# Single_Item_Sensor.net
KiCad netlist of a schematic drawn in EAGLE
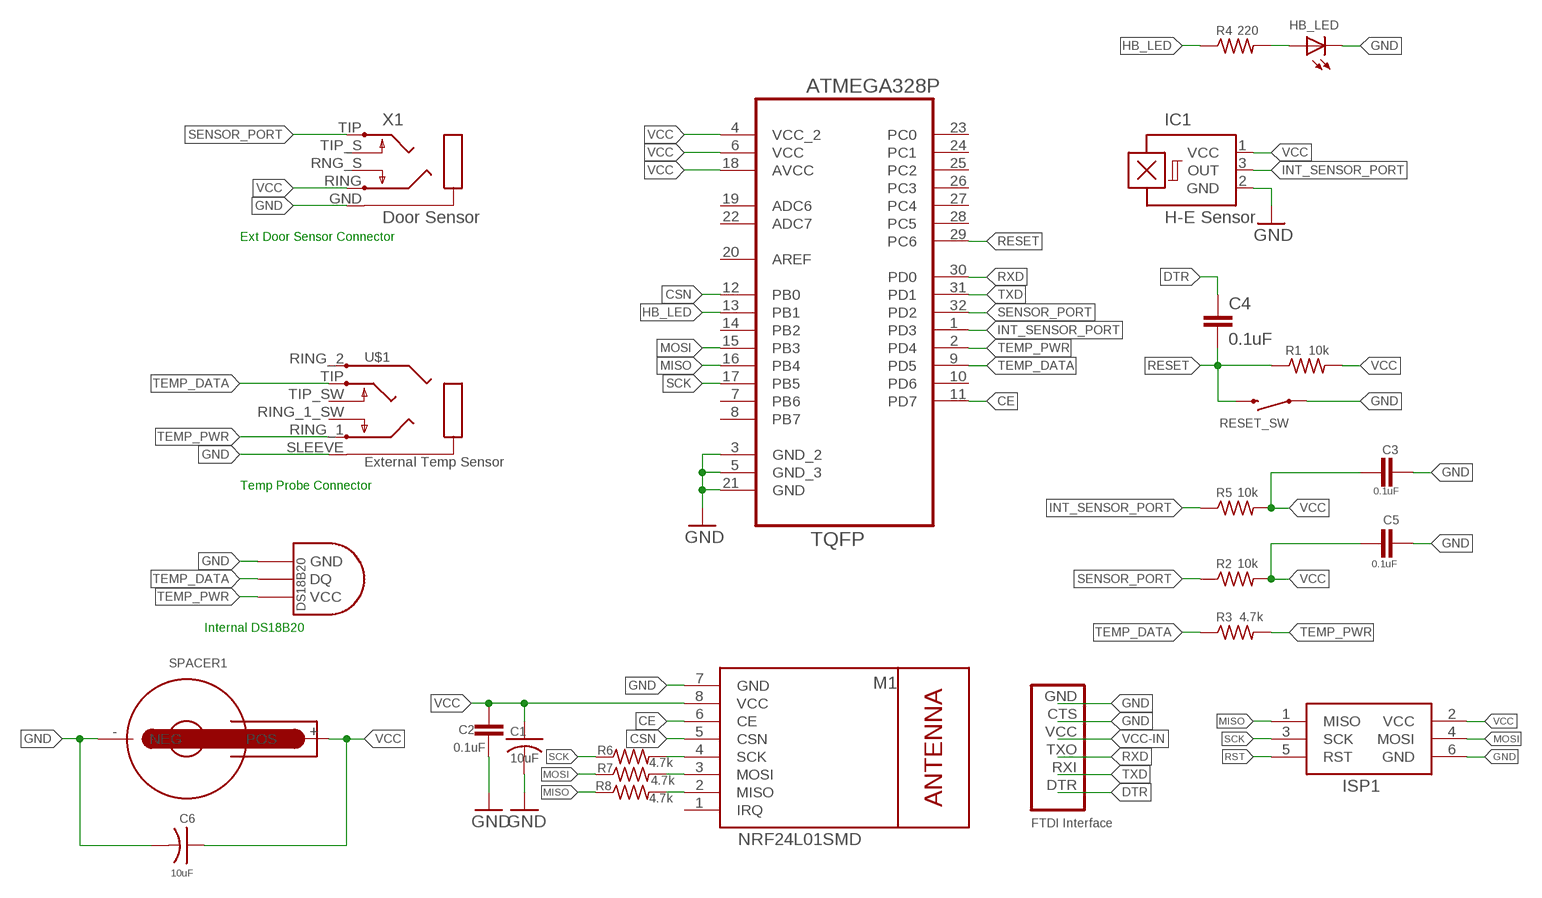
[diagram p0: schematic, sheet 1]

(export (version "E")
  (design (tool "Eeschema 10.0.6"))
  (components
    (comp (ref "C1")
      (value "10uF")
      (footprint "eagle-import:C1206")
      (libsource (lib "eagle-import") (part "C-USC1206"))
    )
    (comp (ref "C2")
      (value "0.1uF")
      (footprint "eagle-import:0805")
      (libsource (lib "eagle-import") (part "CAP0805"))
    )
    (comp (ref "C3")
      (value "0.1uF")
      (footprint "eagle-import:0805")
      (libsource (lib "eagle-import") (part "CAP0805"))
    )
    (comp (ref "C4")
      (value "0.1uF")
      (footprint "eagle-import:0805")
      (libsource (lib "eagle-import") (part "CAP0805"))
    )
    (comp (ref "C5")
      (value "0.1uF")
      (footprint "eagle-import:0805")
      (libsource (lib "eagle-import") (part "CAP0805"))
    )
    (comp (ref "C6")
      (value "10uF")
      (footprint "eagle-import:C1206")
      (libsource (lib "eagle-import") (part "C-USC1206"))
    )
    (comp (ref "HB_LED")
      (value "LEDCHIP-LED0603")
      (footprint "eagle-import:CHIP-LED0603")
      (libsource (lib "eagle-import") (part "LEDCHIP-LED0603"))
    )
    (comp (ref "IC1")
      (value "H-E Sensor")
      (footprint "eagle-import:SIP3-UA")
      (libsource (lib "eagle-import") (part "A12?UA02"))
    )
    (comp (ref "ISP1")
      (value "AVRISP-6")
      (footprint "eagle-import:AVRISP")
      (libsource (lib "eagle-import") (part "AVRISP-6"))
    )
    (comp (ref "M1")
      (value "NRF24L01SMD")
      (footprint "eagle-import:WIRELESS-NRF24L01-SMD")
      (libsource (lib "eagle-import") (part "WIRELESS-NRF24L01SMD"))
    )
    (comp (ref "R1")
      (value "10k")
      (footprint "eagle-import:M0805")
      (libsource (lib "eagle-import") (part "R-US_M0805"))
    )
    (comp (ref "R2")
      (value "10k")
      (footprint "eagle-import:M0805")
      (libsource (lib "eagle-import") (part "R-US_M0805"))
    )
    (comp (ref "R3")
      (value "4.7k")
      (footprint "eagle-import:M0805")
      (libsource (lib "eagle-import") (part "R-US_M0805"))
    )
    (comp (ref "R4")
      (value "220")
      (footprint "eagle-import:M0805")
      (libsource (lib "eagle-import") (part "R-US_M0805"))
    )
    (comp (ref "R5")
      (value "10k")
      (footprint "eagle-import:M0805")
      (libsource (lib "eagle-import") (part "R-US_M0805"))
    )
    (comp (ref "R6")
      (value "4.7k")
      (footprint "eagle-import:M0805")
      (libsource (lib "eagle-import") (part "R-US_M0805"))
    )
    (comp (ref "R7")
      (value "4.7k")
      (footprint "eagle-import:M0805")
      (libsource (lib "eagle-import") (part "R-US_M0805"))
    )
    (comp (ref "R8")
      (value "4.7k")
      (footprint "eagle-import:M0805")
      (libsource (lib "eagle-import") (part "R-US_M0805"))
    )
    (comp (ref "RESET_SW")
      (value "Reset")
      (footprint "eagle-import:TACTILE-SWITCH-1101NE")
      (libsource (lib "eagle-import") (part "SWITCH-MOMENTARY-2-SMD-1101NE"))
    )
    (comp (ref "SPACER1")
      (value "WA-BCPH_SMT_79527141")
      (footprint "eagle-import:79527141")
      (libsource (lib "eagle-import") (part "WA-BCPH_SMT_79527141"))
    )
    (comp (ref "U$1")
      (value "External Temp Sensor")
      (footprint "eagle-import:PJ-242")
      (libsource (lib "eagle-import") (part "PJ-242"))
    )
    (comp (ref "U$2")
      (value "DS1820TO92")
      (footprint "eagle-import:DS1820")
      (libsource (lib "eagle-import") (part "DS1820TO92"))
    )
    (comp (ref "U$3")
      (value "FTDI Interface")
      (footprint "eagle-import:1X6-FTDI")
      (libsource (lib "eagle-import") (part "FTDI-HEADER"))
    )
    (comp (ref "U1")
      (value "ATMEGA328P-AU")
      (footprint "eagle-import:QFP80P900X900X120-32N")
      (libsource (lib "eagle-import") (part "ATMEGA328P-AU"))
    )
    (comp (ref "X1")
      (value "Door Sensor")
      (footprint "eagle-import:PG203J")
      (libsource (lib "eagle-import") (part "PG203JPJ-328"))
    )
  )
  (nets
    (net (code "1") (name "CE") (class "Default")
      (node (ref "M1") (pin "6") (pinfunction "CE_6") (pintype "bidirectional"))
      (node (ref "U1") (pin "11") (pinfunction "PD7_11") (pintype "bidirectional"))
    )
    (net (code "2") (name "CSN") (class "Default")
      (node (ref "M1") (pin "5") (pinfunction "CSN_5") (pintype "bidirectional"))
      (node (ref "U1") (pin "12") (pinfunction "PB0_12") (pintype "bidirectional"))
    )
    (net (code "3") (name "DTR") (class "Default")
      (node (ref "C4") (pin "1") (pinfunction "1_1") (pintype "passive"))
      (node (ref "U$3") (pin "DTR") (pinfunction "DTR_DTR") (pintype "passive"))
    )
    (net (code "4") (name "GND") (class "Default")
      (node (ref "C1") (pin "2") (pinfunction "2_2") (pintype "passive"))
      (node (ref "C2") (pin "2") (pinfunction "2_2") (pintype "passive"))
      (node (ref "C3") (pin "2") (pinfunction "2_2") (pintype "passive"))
      (node (ref "C5") (pin "2") (pinfunction "2_2") (pintype "passive"))
      (node (ref "C6") (pin "2") (pinfunction "2_2") (pintype "passive"))
      (node (ref "HB_LED") (pin "C") (pinfunction "C_C") (pintype "passive"))
      (node (ref "IC1") (pin "2") (pinfunction "GND_2") (pintype "power_in"))
      (node (ref "ISP1") (pin "6") (pinfunction "GND_6") (pintype "power_in"))
      (node (ref "M1") (pin "7") (pinfunction "GND_7") (pintype "power_in"))
      (node (ref "RESET_SW") (pin "P$1") (pinfunction "1_P$1") (pintype "passive"))
      (node (ref "SPACER1") (pin "-") (pinfunction "NEG_-") (pintype "bidirectional"))
      (node (ref "U$1") (pin "SLEEVE") (pinfunction "5_SLEEVE") (pintype "passive"))
      (node (ref "U$2") (pin "GND") (pinfunction "GND_GND") (pintype "power_in"))
      (node (ref "U$3") (pin "CTS") (pinfunction "CTS_CTS") (pintype "passive"))
      (node (ref "U$3") (pin "GND") (pinfunction "GND_GND") (pintype "passive"))
      (node (ref "U1") (pin "21") (pinfunction "GND_21") (pintype "passive"))
      (node (ref "U1") (pin "3") (pinfunction "GND_2_3") (pintype "passive"))
      (node (ref "U1") (pin "5") (pinfunction "GND_3_5") (pintype "passive"))
      (node (ref "X1") (pin "GND") (pinfunction "1_GND") (pintype "passive"))
    )
    (net (code "5") (name "HB_LED") (class "Default")
      (node (ref "R4") (pin "1") (pinfunction "1_1") (pintype "passive"))
      (node (ref "U1") (pin "13") (pinfunction "PB1_13") (pintype "bidirectional"))
    )
    (net (code "6") (name "INT_SENSOR_PORT") (class "Default")
      (node (ref "IC1") (pin "3") (pinfunction "OUT_3") (pintype "output"))
      (node (ref "R5") (pin "1") (pinfunction "1_1") (pintype "passive"))
      (node (ref "U1") (pin "1") (pinfunction "PD3_1") (pintype "bidirectional"))
    )
    (net (code "7") (name "MISO") (class "Default")
      (node (ref "ISP1") (pin "1") (pinfunction "MISO_1") (pintype "input"))
      (node (ref "R8") (pin "1") (pinfunction "1_1") (pintype "passive"))
      (node (ref "U1") (pin "16") (pinfunction "PB4_16") (pintype "bidirectional"))
    )
    (net (code "8") (name "MOSI") (class "Default")
      (node (ref "ISP1") (pin "4") (pinfunction "MOSI_4") (pintype "output"))
      (node (ref "R7") (pin "1") (pinfunction "1_1") (pintype "passive"))
      (node (ref "U1") (pin "15") (pinfunction "PB3_15") (pintype "bidirectional"))
    )
    (net (code "9") (name "Net-(HB_LED-PadA)") (class "Default")
      (node (ref "HB_LED") (pin "A") (pinfunction "A_A") (pintype "passive"))
      (node (ref "R4") (pin "2") (pinfunction "2_2") (pintype "passive"))
    )
    (net (code "10") (name "Net-(M1-MISO)") (class "Default")
      (node (ref "M1") (pin "2") (pinfunction "MISO_2") (pintype "bidirectional"))
      (node (ref "R8") (pin "2") (pinfunction "2_2") (pintype "passive"))
    )
    (net (code "11") (name "Net-(M1-MOSI)") (class "Default")
      (node (ref "M1") (pin "3") (pinfunction "MOSI_3") (pintype "bidirectional"))
      (node (ref "R7") (pin "2") (pinfunction "2_2") (pintype "passive"))
    )
    (net (code "12") (name "Net-(M1-SCK)") (class "Default")
      (node (ref "M1") (pin "4") (pinfunction "SCK_4") (pintype "bidirectional"))
      (node (ref "R6") (pin "2") (pinfunction "2_2") (pintype "passive"))
    )
    (net (code "13") (name "RESET") (class "Default")
      (node (ref "C4") (pin "2") (pinfunction "2_2") (pintype "passive"))
      (node (ref "R1") (pin "1") (pinfunction "1_1") (pintype "passive"))
      (node (ref "RESET_SW") (pin "P$2") (pinfunction "2_P$2") (pintype "passive"))
      (node (ref "U1") (pin "29") (pinfunction "PC6_29") (pintype "bidirectional"))
    )
    (net (code "14") (name "RST") (class "Default")
      (node (ref "ISP1") (pin "5") (pinfunction "RST_5") (pintype "output"))
    )
    (net (code "15") (name "RXD") (class "Default")
      (node (ref "U$3") (pin "TXO") (pinfunction "TXO_TXO") (pintype "passive"))
      (node (ref "U1") (pin "30") (pinfunction "PD0_30") (pintype "bidirectional"))
    )
    (net (code "16") (name "SCK") (class "Default")
      (node (ref "ISP1") (pin "3") (pinfunction "SCK_3") (pintype "output"))
      (node (ref "R6") (pin "1") (pinfunction "1_1") (pintype "passive"))
      (node (ref "U1") (pin "17") (pinfunction "PB5_17") (pintype "bidirectional"))
    )
    (net (code "17") (name "SENSOR_PORT") (class "Default")
      (node (ref "R2") (pin "1") (pinfunction "1_1") (pintype "passive"))
      (node (ref "U1") (pin "32") (pinfunction "PD2_32") (pintype "bidirectional"))
      (node (ref "X1") (pin "TIP") (pinfunction "5_TIP") (pintype "passive"))
    )
    (net (code "18") (name "TEMP_DATA") (class "Default")
      (node (ref "R3") (pin "1") (pinfunction "1_1") (pintype "passive"))
      (node (ref "U$1") (pin "TIP") (pinfunction "6_TIP") (pintype "passive"))
      (node (ref "U$2") (pin "DQ") (pinfunction "DQ_DQ") (pintype "bidirectional"))
      (node (ref "U1") (pin "9") (pinfunction "PD5_9") (pintype "bidirectional"))
    )
    (net (code "19") (name "TEMP_PWR") (class "Default")
      (node (ref "R3") (pin "2") (pinfunction "2_2") (pintype "passive"))
      (node (ref "U$1") (pin "RING_1") (pinfunction "3_RING_1") (pintype "passive"))
      (node (ref "U$2") (pin "VDD") (pinfunction "VCC_VDD") (pintype "power_in"))
      (node (ref "U1") (pin "2") (pinfunction "PD4_2") (pintype "bidirectional"))
    )
    (net (code "20") (name "TXD") (class "Default")
      (node (ref "U$3") (pin "RXI") (pinfunction "RXI_RXI") (pintype "passive"))
      (node (ref "U1") (pin "31") (pinfunction "PD1_31") (pintype "bidirectional"))
    )
    (net (code "21") (name "VCC") (class "Default")
      (node (ref "C1") (pin "1") (pinfunction "1_1") (pintype "passive"))
      (node (ref "C2") (pin "1") (pinfunction "1_1") (pintype "passive"))
      (node (ref "C3") (pin "1") (pinfunction "1_1") (pintype "passive"))
      (node (ref "C5") (pin "1") (pinfunction "1_1") (pintype "passive"))
      (node (ref "C6") (pin "1") (pinfunction "1_1") (pintype "passive"))
      (node (ref "IC1") (pin "1") (pinfunction "VCC_1") (pintype "power_in"))
      (node (ref "ISP1") (pin "2") (pinfunction "VCC_2") (pintype "power_in"))
      (node (ref "M1") (pin "8") (pinfunction "VCC_8") (pintype "power_in"))
      (node (ref "R1") (pin "2") (pinfunction "2_2") (pintype "passive"))
      (node (ref "R2") (pin "2") (pinfunction "2_2") (pintype "passive"))
      (node (ref "R5") (pin "2") (pinfunction "2_2") (pintype "passive"))
      (node (ref "SPACER1") (pin "+") (pinfunction "POS_+") (pintype "bidirectional"))
      (node (ref "U1") (pin "18") (pinfunction "AVCC_18") (pintype "power_in"))
      (node (ref "U1") (pin "4") (pinfunction "VCC_2_4") (pintype "power_in"))
      (node (ref "U1") (pin "6") (pinfunction "VCC_6") (pintype "power_in"))
      (node (ref "X1") (pin "RING") (pinfunction "2_RING") (pintype "passive"))
    )
    (net (code "22") (name "VCC-IN") (class "Default")
      (node (ref "U$3") (pin "VCC") (pinfunction "VCC_VCC") (pintype "passive"))
    )
    (net (code "23") (name "unconnected-(M1-IRQ-Pad1)") (class "Default")
      (node (ref "M1") (pin "1") (pinfunction "IRQ_1") (pintype "bidirectional"))
    )
    (net (code "24") (name "unconnected-(U$1-2-PadRING_2)") (class "Default")
      (node (ref "U$1") (pin "RING_2") (pinfunction "2_RING_2") (pintype "passive"))
    )
    (net (code "25") (name "unconnected-(U$1-4-PadRING_1_SW)") (class "Default")
      (node (ref "U$1") (pin "RING_1_SW") (pinfunction "4_RING_1_SW") (pintype "passive"))
    )
    (net (code "26") (name "unconnected-(U$1-7-PadTIP_SW)") (class "Default")
      (node (ref "U$1") (pin "TIP_SW") (pinfunction "7_TIP_SW") (pintype "passive"))
    )
    (net (code "27") (name "unconnected-(U1-ADC6-Pad19)") (class "Default")
      (node (ref "U1") (pin "19") (pinfunction "ADC6_19") (pintype "input"))
    )
    (net (code "28") (name "unconnected-(U1-ADC7-Pad22)") (class "Default")
      (node (ref "U1") (pin "22") (pinfunction "ADC7_22") (pintype "input"))
    )
    (net (code "29") (name "unconnected-(U1-AREF-Pad20)") (class "Default")
      (node (ref "U1") (pin "20") (pinfunction "AREF_20") (pintype "input"))
    )
    (net (code "30") (name "unconnected-(U1-PB2-Pad14)") (class "Default")
      (node (ref "U1") (pin "14") (pinfunction "PB2_14") (pintype "bidirectional"))
    )
    (net (code "31") (name "unconnected-(U1-PB6-Pad7)") (class "Default")
      (node (ref "U1") (pin "7") (pinfunction "PB6_7") (pintype "bidirectional"))
    )
    (net (code "32") (name "unconnected-(U1-PB7-Pad8)") (class "Default")
      (node (ref "U1") (pin "8") (pinfunction "PB7_8") (pintype "bidirectional"))
    )
    (net (code "33") (name "unconnected-(U1-PC0-Pad23)") (class "Default")
      (node (ref "U1") (pin "23") (pinfunction "PC0_23") (pintype "bidirectional"))
    )
    (net (code "34") (name "unconnected-(U1-PC1-Pad24)") (class "Default")
      (node (ref "U1") (pin "24") (pinfunction "PC1_24") (pintype "bidirectional"))
    )
    (net (code "35") (name "unconnected-(U1-PC2-Pad25)") (class "Default")
      (node (ref "U1") (pin "25") (pinfunction "PC2_25") (pintype "bidirectional"))
    )
    (net (code "36") (name "unconnected-(U1-PC3-Pad26)") (class "Default")
      (node (ref "U1") (pin "26") (pinfunction "PC3_26") (pintype "bidirectional"))
    )
    (net (code "37") (name "unconnected-(U1-PC4-Pad27)") (class "Default")
      (node (ref "U1") (pin "27") (pinfunction "PC4_27") (pintype "bidirectional"))
    )
    (net (code "38") (name "unconnected-(U1-PC5-Pad28)") (class "Default")
      (node (ref "U1") (pin "28") (pinfunction "PC5_28") (pintype "bidirectional"))
    )
    (net (code "39") (name "unconnected-(U1-PD6-Pad10)") (class "Default")
      (node (ref "U1") (pin "10") (pinfunction "PD6_10") (pintype "bidirectional"))
    )
    (net (code "40") (name "unconnected-(X1-3-PadRNG_S)") (class "Default")
      (node (ref "X1") (pin "RNG_S") (pinfunction "3_RNG_S") (pintype "passive"))
    )
    (net (code "41") (name "unconnected-(X1-4-PadTIP_S)") (class "Default")
      (node (ref "X1") (pin "TIP_S") (pinfunction "4_TIP_S") (pintype "passive"))
    )
  )
)
